# PCB-BI8-2x5C3.net
KiCad netlist of a schematic drawn in EAGLE
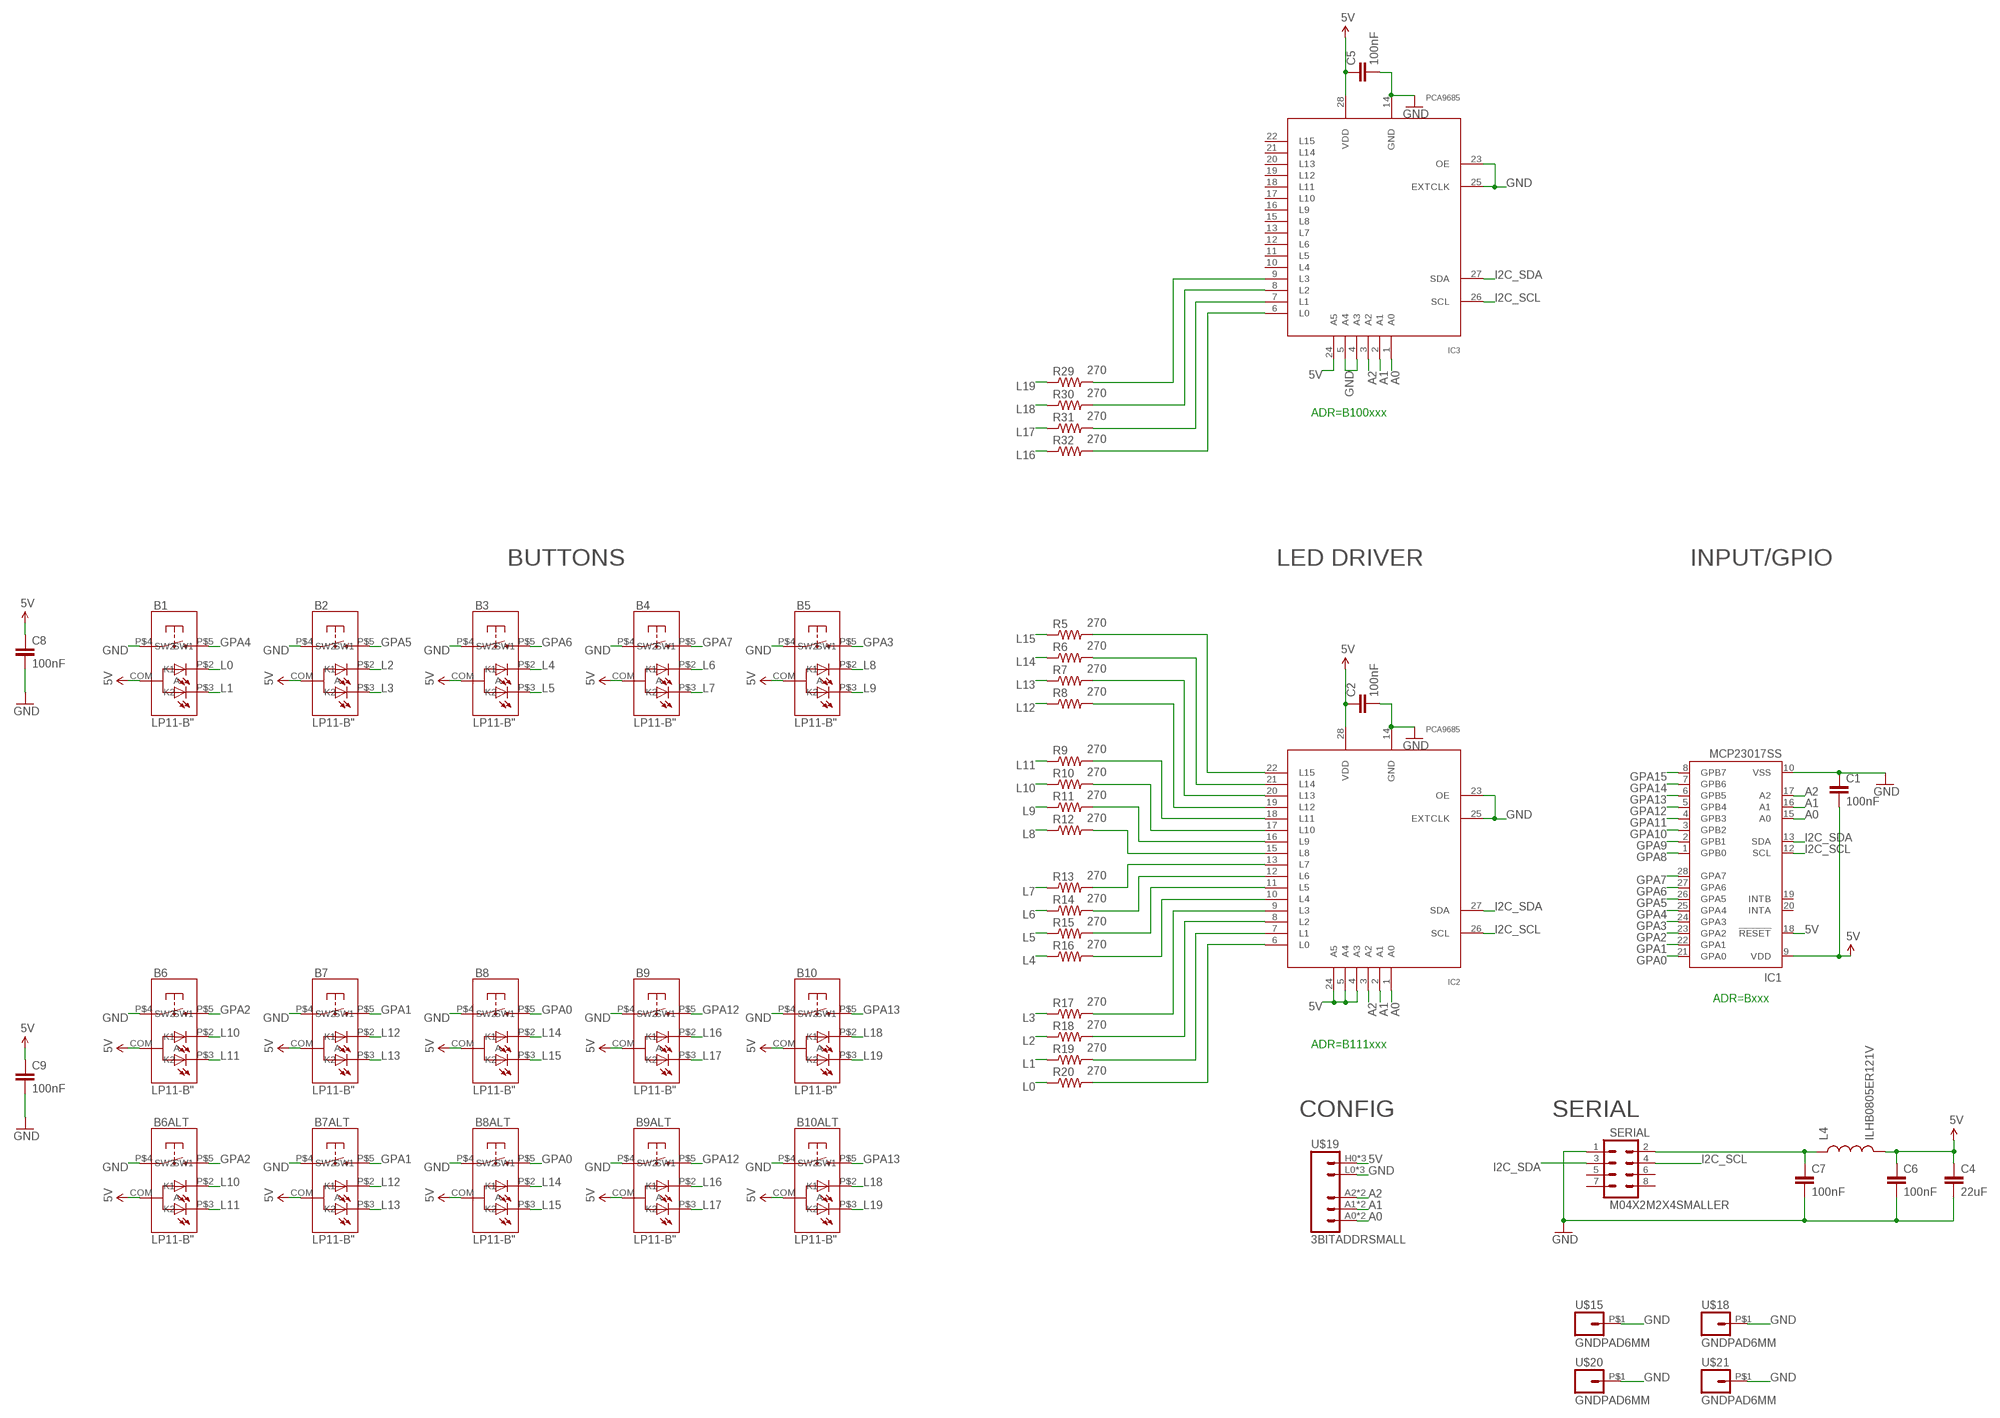
[diagram p0: schematic, sheet 1]

(export (version "E")
  (design (tool "Eeschema 10.0.6"))
  (components
    (comp (ref "B1")
      (value "LP11-B\"")
      (footprint "eagle-import:LP11")
      (libsource (lib "eagle-import") (part "LP11-B{dblquote}"))
    )
    (comp (ref "B2")
      (value "LP11-B\"")
      (footprint "eagle-import:LP11")
      (libsource (lib "eagle-import") (part "LP11-B{dblquote}"))
    )
    (comp (ref "B3")
      (value "LP11-B\"")
      (footprint "eagle-import:LP11")
      (libsource (lib "eagle-import") (part "LP11-B{dblquote}"))
    )
    (comp (ref "B4")
      (value "LP11-B\"")
      (footprint "eagle-import:LP11")
      (libsource (lib "eagle-import") (part "LP11-B{dblquote}"))
    )
    (comp (ref "B5")
      (value "LP11-B\"")
      (footprint "eagle-import:LP11")
      (libsource (lib "eagle-import") (part "LP11-B{dblquote}"))
    )
    (comp (ref "B6")
      (value "LP11-B\"")
      (footprint "eagle-import:LP11")
      (libsource (lib "eagle-import") (part "LP11-B{dblquote}"))
    )
    (comp (ref "B6ALT")
      (value "LP11-B\"")
      (footprint "eagle-import:LP11")
      (libsource (lib "eagle-import") (part "LP11-B{dblquote}"))
    )
    (comp (ref "B7")
      (value "LP11-B\"")
      (footprint "eagle-import:LP11")
      (libsource (lib "eagle-import") (part "LP11-B{dblquote}"))
    )
    (comp (ref "B7ALT")
      (value "LP11-B\"")
      (footprint "eagle-import:LP11")
      (libsource (lib "eagle-import") (part "LP11-B{dblquote}"))
    )
    (comp (ref "B8")
      (value "LP11-B\"")
      (footprint "eagle-import:LP11")
      (libsource (lib "eagle-import") (part "LP11-B{dblquote}"))
    )
    (comp (ref "B8ALT")
      (value "LP11-B\"")
      (footprint "eagle-import:LP11")
      (libsource (lib "eagle-import") (part "LP11-B{dblquote}"))
    )
    (comp (ref "B9")
      (value "LP11-B\"")
      (footprint "eagle-import:LP11")
      (libsource (lib "eagle-import") (part "LP11-B{dblquote}"))
    )
    (comp (ref "B9ALT")
      (value "LP11-B\"")
      (footprint "eagle-import:LP11")
      (libsource (lib "eagle-import") (part "LP11-B{dblquote}"))
    )
    (comp (ref "B10")
      (value "LP11-B\"")
      (footprint "eagle-import:LP11")
      (libsource (lib "eagle-import") (part "LP11-B{dblquote}"))
    )
    (comp (ref "B10ALT")
      (value "LP11-B\"")
      (footprint "eagle-import:LP11")
      (libsource (lib "eagle-import") (part "LP11-B{dblquote}"))
    )
    (comp (ref "C1")
      (value "100nF")
      (footprint "eagle-import:0603-CAP")
      (libsource (lib "eagle-import") (part "CAP0603-CAP"))
    )
    (comp (ref "C2")
      (value "100nF")
      (footprint "eagle-import:0603-CAP")
      (libsource (lib "eagle-import") (part "CAP0603-CAP"))
    )
    (comp (ref "C4")
      (value "22uF")
      (footprint "eagle-import:0805")
      (libsource (lib "eagle-import") (part "CAP0805"))
    )
    (comp (ref "C5")
      (value "100nF")
      (footprint "eagle-import:0603-CAP")
      (libsource (lib "eagle-import") (part "CAP0603-CAP"))
    )
    (comp (ref "C6")
      (value "100nF")
      (footprint "eagle-import:0603-CAP")
      (libsource (lib "eagle-import") (part "CAP0603-CAP"))
    )
    (comp (ref "C7")
      (value "100nF")
      (footprint "eagle-import:0603-CAP")
      (libsource (lib "eagle-import") (part "CAP0603-CAP"))
    )
    (comp (ref "C8")
      (value "100nF")
      (footprint "eagle-import:0603-CAP")
      (libsource (lib "eagle-import") (part "CAP0603-CAP"))
    )
    (comp (ref "C9")
      (value "100nF")
      (footprint "eagle-import:0603-CAP")
      (libsource (lib "eagle-import") (part "CAP0603-CAP"))
    )
    (comp (ref "IC1")
      (value "MCP23017SS")
      (footprint "eagle-import:SSOP28")
      (fields
        (field (name "MF") "MICROCHIP")
        (field (name "MPN") "MCP23017-E/SS")
        (field (name "MPN_1") "MCP23017-E/SS")
        (field (name "OC_FARNELL") "1467674")
        (field (name "OC_NEWARK") "31K2960")
      )
      (libsource (lib "eagle-import") (part "MCP23017SS"))
    )
    (comp (ref "IC2")
      (value "PCA9685")
      (footprint "eagle-import:TSSOP28")
      (libsource (lib "eagle-import") (part "PCA9685"))
    )
    (comp (ref "IC3")
      (value "PCA9685")
      (footprint "eagle-import:TSSOP28")
      (libsource (lib "eagle-import") (part "PCA9685"))
    )
    (comp (ref "L4")
      (value "ILHB0805ER121V")
      (footprint "eagle-import:0805")
      (libsource (lib "eagle-import") (part "INDUCTOR0805"))
    )
    (comp (ref "R5")
      (value "270")
      (footprint "eagle-import:0603-RES")
      (libsource (lib "eagle-import") (part "RESISTOR0603-RES"))
    )
    (comp (ref "R6")
      (value "270")
      (footprint "eagle-import:0603-RES")
      (libsource (lib "eagle-import") (part "RESISTOR0603-RES"))
    )
    (comp (ref "R7")
      (value "270")
      (footprint "eagle-import:0603-RES")
      (libsource (lib "eagle-import") (part "RESISTOR0603-RES"))
    )
    (comp (ref "R8")
      (value "270")
      (footprint "eagle-import:0603-RES")
      (libsource (lib "eagle-import") (part "RESISTOR0603-RES"))
    )
    (comp (ref "R9")
      (value "270")
      (footprint "eagle-import:0603-RES")
      (libsource (lib "eagle-import") (part "RESISTOR0603-RES"))
    )
    (comp (ref "R10")
      (value "270")
      (footprint "eagle-import:0603-RES")
      (libsource (lib "eagle-import") (part "RESISTOR0603-RES"))
    )
    (comp (ref "R11")
      (value "270")
      (footprint "eagle-import:0603-RES")
      (libsource (lib "eagle-import") (part "RESISTOR0603-RES"))
    )
    (comp (ref "R12")
      (value "270")
      (footprint "eagle-import:0603-RES")
      (libsource (lib "eagle-import") (part "RESISTOR0603-RES"))
    )
    (comp (ref "R13")
      (value "270")
      (footprint "eagle-import:0603-RES")
      (libsource (lib "eagle-import") (part "RESISTOR0603-RES"))
    )
    (comp (ref "R14")
      (value "270")
      (footprint "eagle-import:0603-RES")
      (libsource (lib "eagle-import") (part "RESISTOR0603-RES"))
    )
    (comp (ref "R15")
      (value "270")
      (footprint "eagle-import:0603-RES")
      (libsource (lib "eagle-import") (part "RESISTOR0603-RES"))
    )
    (comp (ref "R16")
      (value "270")
      (footprint "eagle-import:0603-RES")
      (libsource (lib "eagle-import") (part "RESISTOR0603-RES"))
    )
    (comp (ref "R17")
      (value "270")
      (footprint "eagle-import:0603-RES")
      (libsource (lib "eagle-import") (part "RESISTOR0603-RES"))
    )
    (comp (ref "R18")
      (value "270")
      (footprint "eagle-import:0603-RES")
      (libsource (lib "eagle-import") (part "RESISTOR0603-RES"))
    )
    (comp (ref "R19")
      (value "270")
      (footprint "eagle-import:0603-RES")
      (libsource (lib "eagle-import") (part "RESISTOR0603-RES"))
    )
    (comp (ref "R20")
      (value "270")
      (footprint "eagle-import:0603-RES")
      (libsource (lib "eagle-import") (part "RESISTOR0603-RES"))
    )
    (comp (ref "R29")
      (value "270")
      (footprint "eagle-import:0603-RES")
      (libsource (lib "eagle-import") (part "RESISTOR0603-RES"))
    )
    (comp (ref "R30")
      (value "270")
      (footprint "eagle-import:0603-RES")
      (libsource (lib "eagle-import") (part "RESISTOR0603-RES"))
    )
    (comp (ref "R31")
      (value "270")
      (footprint "eagle-import:0603-RES")
      (libsource (lib "eagle-import") (part "RESISTOR0603-RES"))
    )
    (comp (ref "R32")
      (value "270")
      (footprint "eagle-import:0603-RES")
      (libsource (lib "eagle-import") (part "RESISTOR0603-RES"))
    )
    (comp (ref "SERIAL")
      (value "M04X2M2X4SMALLER")
      (footprint "eagle-import:M2X4SMALLER")
      (libsource (lib "eagle-import") (part "M04X2M2X4SMALLER"))
    )
    (comp (ref "U$15")
      (value "GNDPAD6MM")
      (footprint "eagle-import:3.2MMPAD6MM")
      (libsource (lib "eagle-import") (part "GNDPAD6MM"))
    )
    (comp (ref "U$18")
      (value "GNDPAD6MM")
      (footprint "eagle-import:3.2MMPAD6MM")
      (libsource (lib "eagle-import") (part "GNDPAD6MM"))
    )
    (comp (ref "U$19")
      (value "3BITADDRSMALL")
      (footprint "eagle-import:3BITADDR_SMALL")
      (libsource (lib "eagle-import") (part "3BITADDRSMALL"))
    )
    (comp (ref "U$20")
      (value "GNDPAD6MM")
      (footprint "eagle-import:3.2MMPAD6MM")
      (libsource (lib "eagle-import") (part "GNDPAD6MM"))
    )
    (comp (ref "U$21")
      (value "GNDPAD6MM")
      (footprint "eagle-import:3.2MMPAD6MM")
      (libsource (lib "eagle-import") (part "GNDPAD6MM"))
    )
  )
  (nets
    (net (code "1") (name "5V") (class "Default")
      (node (ref "B1") (pin "COM") (pinfunction "A_COM") (pintype "bidirectional"))
      (node (ref "B10") (pin "COM") (pinfunction "A_COM") (pintype "bidirectional"))
      (node (ref "B10ALT") (pin "COM") (pinfunction "A_COM") (pintype "bidirectional"))
      (node (ref "B2") (pin "COM") (pinfunction "A_COM") (pintype "bidirectional"))
      (node (ref "B3") (pin "COM") (pinfunction "A_COM") (pintype "bidirectional"))
      (node (ref "B4") (pin "COM") (pinfunction "A_COM") (pintype "bidirectional"))
      (node (ref "B5") (pin "COM") (pinfunction "A_COM") (pintype "bidirectional"))
      (node (ref "B6") (pin "COM") (pinfunction "A_COM") (pintype "bidirectional"))
      (node (ref "B6ALT") (pin "COM") (pinfunction "A_COM") (pintype "bidirectional"))
      (node (ref "B7") (pin "COM") (pinfunction "A_COM") (pintype "bidirectional"))
      (node (ref "B7ALT") (pin "COM") (pinfunction "A_COM") (pintype "bidirectional"))
      (node (ref "B8") (pin "COM") (pinfunction "A_COM") (pintype "bidirectional"))
      (node (ref "B8ALT") (pin "COM") (pinfunction "A_COM") (pintype "bidirectional"))
      (node (ref "B9") (pin "COM") (pinfunction "A_COM") (pintype "bidirectional"))
      (node (ref "B9ALT") (pin "COM") (pinfunction "A_COM") (pintype "bidirectional"))
      (node (ref "C1") (pin "2") (pinfunction "2_2") (pintype "passive"))
      (node (ref "C2") (pin "1") (pinfunction "1_1") (pintype "passive"))
      (node (ref "C4") (pin "1") (pinfunction "1_1") (pintype "passive"))
      (node (ref "C5") (pin "1") (pinfunction "1_1") (pintype "passive"))
      (node (ref "C6") (pin "1") (pinfunction "1_1") (pintype "passive"))
      (node (ref "C8") (pin "1") (pinfunction "1_1") (pintype "passive"))
      (node (ref "C9") (pin "1") (pinfunction "1_1") (pintype "passive"))
      (node (ref "IC1") (pin "18") (pinfunction "~{RESET}_18") (pintype "input"))
      (node (ref "IC1") (pin "9") (pinfunction "VDD_9") (pintype "power_in"))
      (node (ref "IC2") (pin "24") (pinfunction "A5_24") (pintype "input"))
      (node (ref "IC2") (pin "28") (pinfunction "VDD_28") (pintype "power_in"))
      (node (ref "IC2") (pin "4") (pinfunction "A3_4") (pintype "input"))
      (node (ref "IC2") (pin "5") (pinfunction "A4_5") (pintype "input"))
      (node (ref "IC3") (pin "24") (pinfunction "A5_24") (pintype "input"))
      (node (ref "IC3") (pin "28") (pinfunction "VDD_28") (pintype "power_in"))
      (node (ref "L4") (pin "2") (pinfunction "2_2") (pintype "passive"))
      (node (ref "U$19") (pin "H0") (pinfunction "VCC_H0") (pintype "passive"))
      (node (ref "U$19") (pin "H1") (pinfunction "VCC_H1") (pintype "passive"))
      (node (ref "U$19") (pin "H2") (pinfunction "VCC_H2") (pintype "passive"))
    )
    (net (code "2") (name "A0") (class "Default")
      (node (ref "IC1") (pin "15") (pinfunction "A0_15") (pintype "input"))
      (node (ref "IC2") (pin "1") (pinfunction "A0_1") (pintype "input"))
      (node (ref "IC3") (pin "1") (pinfunction "A0_1") (pintype "input"))
      (node (ref "U$19") (pin "A0") (pinfunction "A0_A0") (pintype "passive"))
      (node (ref "U$19") (pin "AS0") (pinfunction "A0_AS0") (pintype "passive"))
    )
    (net (code "3") (name "A1") (class "Default")
      (node (ref "IC1") (pin "16") (pinfunction "A1_16") (pintype "input"))
      (node (ref "IC2") (pin "2") (pinfunction "A1_2") (pintype "input"))
      (node (ref "IC3") (pin "2") (pinfunction "A1_2") (pintype "input"))
      (node (ref "U$19") (pin "A1") (pinfunction "A1_A1") (pintype "passive"))
      (node (ref "U$19") (pin "AS1") (pinfunction "A1_AS1") (pintype "passive"))
    )
    (net (code "4") (name "A2") (class "Default")
      (node (ref "IC1") (pin "17") (pinfunction "A2_17") (pintype "input"))
      (node (ref "IC2") (pin "3") (pinfunction "A2_3") (pintype "input"))
      (node (ref "IC3") (pin "3") (pinfunction "A2_3") (pintype "input"))
      (node (ref "U$19") (pin "A2") (pinfunction "A2_A2") (pintype "passive"))
      (node (ref "U$19") (pin "AS2") (pinfunction "A2_AS2") (pintype "passive"))
    )
    (net (code "5") (name "GND") (class "Default")
      (node (ref "B1") (pin "P$4") (pinfunction "SW1_P$4") (pintype "bidirectional"))
      (node (ref "B10") (pin "P$4") (pinfunction "SW1_P$4") (pintype "bidirectional"))
      (node (ref "B10ALT") (pin "P$4") (pinfunction "SW1_P$4") (pintype "bidirectional"))
      (node (ref "B2") (pin "P$4") (pinfunction "SW1_P$4") (pintype "bidirectional"))
      (node (ref "B3") (pin "P$4") (pinfunction "SW1_P$4") (pintype "bidirectional"))
      (node (ref "B4") (pin "P$4") (pinfunction "SW1_P$4") (pintype "bidirectional"))
      (node (ref "B5") (pin "P$4") (pinfunction "SW1_P$4") (pintype "bidirectional"))
      (node (ref "B6") (pin "P$4") (pinfunction "SW1_P$4") (pintype "bidirectional"))
      (node (ref "B6ALT") (pin "P$4") (pinfunction "SW1_P$4") (pintype "bidirectional"))
      (node (ref "B7") (pin "P$4") (pinfunction "SW1_P$4") (pintype "bidirectional"))
      (node (ref "B7ALT") (pin "P$4") (pinfunction "SW1_P$4") (pintype "bidirectional"))
      (node (ref "B8") (pin "P$4") (pinfunction "SW1_P$4") (pintype "bidirectional"))
      (node (ref "B8ALT") (pin "P$4") (pinfunction "SW1_P$4") (pintype "bidirectional"))
      (node (ref "B9") (pin "P$4") (pinfunction "SW1_P$4") (pintype "bidirectional"))
      (node (ref "B9ALT") (pin "P$4") (pinfunction "SW1_P$4") (pintype "bidirectional"))
      (node (ref "C1") (pin "1") (pinfunction "1_1") (pintype "passive"))
      (node (ref "C2") (pin "2") (pinfunction "2_2") (pintype "passive"))
      (node (ref "C4") (pin "2") (pinfunction "2_2") (pintype "passive"))
      (node (ref "C5") (pin "2") (pinfunction "2_2") (pintype "passive"))
      (node (ref "C6") (pin "2") (pinfunction "2_2") (pintype "passive"))
      (node (ref "C7") (pin "2") (pinfunction "2_2") (pintype "passive"))
      (node (ref "C8") (pin "2") (pinfunction "2_2") (pintype "passive"))
      (node (ref "C9") (pin "2") (pinfunction "2_2") (pintype "passive"))
      (node (ref "IC1") (pin "10") (pinfunction "VSS_10") (pintype "power_in"))
      (node (ref "IC2") (pin "14") (pinfunction "GND_14") (pintype "power_in"))
      (node (ref "IC2") (pin "23") (pinfunction "OE_23") (pintype "input"))
      (node (ref "IC2") (pin "25") (pinfunction "EXTCLK_25") (pintype "input"))
      (node (ref "IC3") (pin "14") (pinfunction "GND_14") (pintype "power_in"))
      (node (ref "IC3") (pin "23") (pinfunction "OE_23") (pintype "input"))
      (node (ref "IC3") (pin "25") (pinfunction "EXTCLK_25") (pintype "input"))
      (node (ref "IC3") (pin "4") (pinfunction "A3_4") (pintype "input"))
      (node (ref "IC3") (pin "5") (pinfunction "A4_5") (pintype "input"))
      (node (ref "SERIAL") (pin "1") (pinfunction "1_1") (pintype "passive"))
      (node (ref "U$15") (pin "P$1") (pinfunction "1_P$1") (pintype "passive"))
      (node (ref "U$18") (pin "P$1") (pinfunction "1_P$1") (pintype "passive"))
      (node (ref "U$19") (pin "L0") (pinfunction "GND_L0") (pintype "passive"))
      (node (ref "U$19") (pin "L1") (pinfunction "GND_L1") (pintype "passive"))
      (node (ref "U$19") (pin "L2") (pinfunction "GND_L2") (pintype "passive"))
      (node (ref "U$20") (pin "P$1") (pinfunction "1_P$1") (pintype "passive"))
      (node (ref "U$21") (pin "P$1") (pinfunction "1_P$1") (pintype "passive"))
    )
    (net (code "6") (name "GPA0") (class "Default")
      (node (ref "B8") (pin "P$5") (pinfunction "SW2_P$5") (pintype "bidirectional"))
      (node (ref "B8ALT") (pin "P$5") (pinfunction "SW2_P$5") (pintype "bidirectional"))
      (node (ref "IC1") (pin "21") (pinfunction "GPA0_21") (pintype "bidirectional"))
    )
    (net (code "7") (name "GPA1") (class "Default")
      (node (ref "B7") (pin "P$5") (pinfunction "SW2_P$5") (pintype "bidirectional"))
      (node (ref "B7ALT") (pin "P$5") (pinfunction "SW2_P$5") (pintype "bidirectional"))
      (node (ref "IC1") (pin "22") (pinfunction "GPA1_22") (pintype "bidirectional"))
    )
    (net (code "8") (name "GPA2") (class "Default")
      (node (ref "B6") (pin "P$5") (pinfunction "SW2_P$5") (pintype "bidirectional"))
      (node (ref "B6ALT") (pin "P$5") (pinfunction "SW2_P$5") (pintype "bidirectional"))
      (node (ref "IC1") (pin "23") (pinfunction "GPA2_23") (pintype "bidirectional"))
    )
    (net (code "9") (name "GPA3") (class "Default")
      (node (ref "B5") (pin "P$5") (pinfunction "SW2_P$5") (pintype "bidirectional"))
      (node (ref "IC1") (pin "24") (pinfunction "GPA3_24") (pintype "bidirectional"))
    )
    (net (code "10") (name "GPA4") (class "Default")
      (node (ref "B1") (pin "P$5") (pinfunction "SW2_P$5") (pintype "bidirectional"))
      (node (ref "IC1") (pin "25") (pinfunction "GPA4_25") (pintype "bidirectional"))
    )
    (net (code "11") (name "GPA5") (class "Default")
      (node (ref "B2") (pin "P$5") (pinfunction "SW2_P$5") (pintype "bidirectional"))
      (node (ref "IC1") (pin "26") (pinfunction "GPA5_26") (pintype "bidirectional"))
    )
    (net (code "12") (name "GPA6") (class "Default")
      (node (ref "B3") (pin "P$5") (pinfunction "SW2_P$5") (pintype "bidirectional"))
      (node (ref "IC1") (pin "27") (pinfunction "GPA6_27") (pintype "bidirectional"))
    )
    (net (code "13") (name "GPA7") (class "Default")
      (node (ref "B4") (pin "P$5") (pinfunction "SW2_P$5") (pintype "bidirectional"))
      (node (ref "IC1") (pin "28") (pinfunction "GPA7_28") (pintype "bidirectional"))
    )
    (net (code "14") (name "GPA8") (class "Default")
      (node (ref "IC1") (pin "1") (pinfunction "GPB0_1") (pintype "bidirectional"))
    )
    (net (code "15") (name "GPA9") (class "Default")
      (node (ref "IC1") (pin "2") (pinfunction "GPB1_2") (pintype "bidirectional"))
    )
    (net (code "16") (name "GPA10") (class "Default")
      (node (ref "IC1") (pin "3") (pinfunction "GPB2_3") (pintype "bidirectional"))
    )
    (net (code "17") (name "GPA11") (class "Default")
      (node (ref "IC1") (pin "4") (pinfunction "GPB3_4") (pintype "bidirectional"))
    )
    (net (code "18") (name "GPA12") (class "Default")
      (node (ref "B9") (pin "P$5") (pinfunction "SW2_P$5") (pintype "bidirectional"))
      (node (ref "B9ALT") (pin "P$5") (pinfunction "SW2_P$5") (pintype "bidirectional"))
      (node (ref "IC1") (pin "5") (pinfunction "GPB4_5") (pintype "bidirectional"))
    )
    (net (code "19") (name "GPA13") (class "Default")
      (node (ref "B10") (pin "P$5") (pinfunction "SW2_P$5") (pintype "bidirectional"))
      (node (ref "B10ALT") (pin "P$5") (pinfunction "SW2_P$5") (pintype "bidirectional"))
      (node (ref "IC1") (pin "6") (pinfunction "GPB5_6") (pintype "bidirectional"))
    )
    (net (code "20") (name "GPA14") (class "Default")
      (node (ref "IC1") (pin "7") (pinfunction "GPB6_7") (pintype "bidirectional"))
    )
    (net (code "21") (name "GPA15") (class "Default")
      (node (ref "IC1") (pin "8") (pinfunction "GPB7_8") (pintype "bidirectional"))
    )
    (net (code "22") (name "I2C_SCL") (class "Default")
      (node (ref "IC1") (pin "12") (pinfunction "SCL_12") (pintype "input"))
      (node (ref "IC2") (pin "26") (pinfunction "SCL_26") (pintype "input"))
      (node (ref "IC3") (pin "26") (pinfunction "SCL_26") (pintype "input"))
      (node (ref "SERIAL") (pin "4") (pinfunction "4_4") (pintype "passive"))
    )
    (net (code "23") (name "I2C_SDA") (class "Default")
      (node (ref "IC1") (pin "13") (pinfunction "SDA_13") (pintype "bidirectional"))
      (node (ref "IC2") (pin "27") (pinfunction "SDA_27") (pintype "input"))
      (node (ref "IC3") (pin "27") (pinfunction "SDA_27") (pintype "input"))
      (node (ref "SERIAL") (pin "3") (pinfunction "3_3") (pintype "passive"))
    )
    (net (code "24") (name "L0") (class "Default")
      (node (ref "B1") (pin "P$2") (pinfunction "K1_P$2") (pintype "bidirectional"))
      (node (ref "R20") (pin "1") (pinfunction "1_1") (pintype "passive"))
    )
    (net (code "25") (name "L1") (class "Default")
      (node (ref "B1") (pin "P$3") (pinfunction "K2_P$3") (pintype "bidirectional"))
      (node (ref "R19") (pin "1") (pinfunction "1_1") (pintype "passive"))
    )
    (net (code "26") (name "L2") (class "Default")
      (node (ref "B2") (pin "P$2") (pinfunction "K1_P$2") (pintype "bidirectional"))
      (node (ref "R18") (pin "1") (pinfunction "1_1") (pintype "passive"))
    )
    (net (code "27") (name "L3") (class "Default")
      (node (ref "B2") (pin "P$3") (pinfunction "K2_P$3") (pintype "bidirectional"))
      (node (ref "R17") (pin "1") (pinfunction "1_1") (pintype "passive"))
    )
    (net (code "28") (name "L4") (class "Default")
      (node (ref "B3") (pin "P$2") (pinfunction "K1_P$2") (pintype "bidirectional"))
      (node (ref "R16") (pin "1") (pinfunction "1_1") (pintype "passive"))
    )
    (net (code "29") (name "L5") (class "Default")
      (node (ref "B3") (pin "P$3") (pinfunction "K2_P$3") (pintype "bidirectional"))
      (node (ref "R15") (pin "1") (pinfunction "1_1") (pintype "passive"))
    )
    (net (code "30") (name "L6") (class "Default")
      (node (ref "B4") (pin "P$2") (pinfunction "K1_P$2") (pintype "bidirectional"))
      (node (ref "R14") (pin "1") (pinfunction "1_1") (pintype "passive"))
    )
    (net (code "31") (name "L7") (class "Default")
      (node (ref "B4") (pin "P$3") (pinfunction "K2_P$3") (pintype "bidirectional"))
      (node (ref "R13") (pin "1") (pinfunction "1_1") (pintype "passive"))
    )
    (net (code "32") (name "L8") (class "Default")
      (node (ref "B5") (pin "P$2") (pinfunction "K1_P$2") (pintype "bidirectional"))
      (node (ref "R12") (pin "1") (pinfunction "1_1") (pintype "passive"))
    )
    (net (code "33") (name "L9") (class "Default")
      (node (ref "B5") (pin "P$3") (pinfunction "K2_P$3") (pintype "bidirectional"))
      (node (ref "R11") (pin "1") (pinfunction "1_1") (pintype "passive"))
    )
    (net (code "34") (name "L10") (class "Default")
      (node (ref "B6") (pin "P$2") (pinfunction "K1_P$2") (pintype "bidirectional"))
      (node (ref "B6ALT") (pin "P$2") (pinfunction "K1_P$2") (pintype "bidirectional"))
      (node (ref "R10") (pin "1") (pinfunction "1_1") (pintype "passive"))
    )
    (net (code "35") (name "L11") (class "Default")
      (node (ref "B6") (pin "P$3") (pinfunction "K2_P$3") (pintype "bidirectional"))
      (node (ref "B6ALT") (pin "P$3") (pinfunction "K2_P$3") (pintype "bidirectional"))
      (node (ref "R9") (pin "1") (pinfunction "1_1") (pintype "passive"))
    )
    (net (code "36") (name "L12") (class "Default")
      (node (ref "B7") (pin "P$2") (pinfunction "K1_P$2") (pintype "bidirectional"))
      (node (ref "B7ALT") (pin "P$2") (pinfunction "K1_P$2") (pintype "bidirectional"))
      (node (ref "R8") (pin "1") (pinfunction "1_1") (pintype "passive"))
    )
    (net (code "37") (name "L13") (class "Default")
      (node (ref "B7") (pin "P$3") (pinfunction "K2_P$3") (pintype "bidirectional"))
      (node (ref "B7ALT") (pin "P$3") (pinfunction "K2_P$3") (pintype "bidirectional"))
      (node (ref "R7") (pin "1") (pinfunction "1_1") (pintype "passive"))
    )
    (net (code "38") (name "L14") (class "Default")
      (node (ref "B8") (pin "P$2") (pinfunction "K1_P$2") (pintype "bidirectional"))
      (node (ref "B8ALT") (pin "P$2") (pinfunction "K1_P$2") (pintype "bidirectional"))
      (node (ref "R6") (pin "1") (pinfunction "1_1") (pintype "passive"))
    )
    (net (code "39") (name "L15") (class "Default")
      (node (ref "B8") (pin "P$3") (pinfunction "K2_P$3") (pintype "bidirectional"))
      (node (ref "B8ALT") (pin "P$3") (pinfunction "K2_P$3") (pintype "bidirectional"))
      (node (ref "R5") (pin "1") (pinfunction "1_1") (pintype "passive"))
    )
    (net (code "40") (name "L16") (class "Default")
      (node (ref "B9") (pin "P$2") (pinfunction "K1_P$2") (pintype "bidirectional"))
      (node (ref "B9ALT") (pin "P$2") (pinfunction "K1_P$2") (pintype "bidirectional"))
      (node (ref "R32") (pin "1") (pinfunction "1_1") (pintype "passive"))
    )
    (net (code "41") (name "L17") (class "Default")
      (node (ref "B9") (pin "P$3") (pinfunction "K2_P$3") (pintype "bidirectional"))
      (node (ref "B9ALT") (pin "P$3") (pinfunction "K2_P$3") (pintype "bidirectional"))
      (node (ref "R31") (pin "1") (pinfunction "1_1") (pintype "passive"))
    )
    (net (code "42") (name "L18") (class "Default")
      (node (ref "B10") (pin "P$2") (pinfunction "K1_P$2") (pintype "bidirectional"))
      (node (ref "B10ALT") (pin "P$2") (pinfunction "K1_P$2") (pintype "bidirectional"))
      (node (ref "R30") (pin "1") (pinfunction "1_1") (pintype "passive"))
    )
    (net (code "43") (name "L19") (class "Default")
      (node (ref "B10") (pin "P$3") (pinfunction "K2_P$3") (pintype "bidirectional"))
      (node (ref "B10ALT") (pin "P$3") (pinfunction "K2_P$3") (pintype "bidirectional"))
      (node (ref "R29") (pin "1") (pinfunction "1_1") (pintype "passive"))
    )
    (net (code "44") (name "Net-(C7-Pad1)") (class "Default")
      (node (ref "C7") (pin "1") (pinfunction "1_1") (pintype "passive"))
      (node (ref "L4") (pin "1") (pinfunction "1_1") (pintype "passive"))
      (node (ref "SERIAL") (pin "2") (pinfunction "2_2") (pintype "passive"))
    )
    (net (code "45") (name "Net-(IC2-L0)") (class "Default")
      (node (ref "IC2") (pin "6") (pinfunction "L0_6") (pintype "output"))
      (node (ref "R20") (pin "2") (pinfunction "2_2") (pintype "passive"))
    )
    (net (code "46") (name "Net-(IC2-L1)") (class "Default")
      (node (ref "IC2") (pin "7") (pinfunction "L1_7") (pintype "output"))
      (node (ref "R19") (pin "2") (pinfunction "2_2") (pintype "passive"))
    )
    (net (code "47") (name "Net-(IC2-L2)") (class "Default")
      (node (ref "IC2") (pin "8") (pinfunction "L2_8") (pintype "output"))
      (node (ref "R18") (pin "2") (pinfunction "2_2") (pintype "passive"))
    )
    (net (code "48") (name "Net-(IC2-L3)") (class "Default")
      (node (ref "IC2") (pin "9") (pinfunction "L3_9") (pintype "output"))
      (node (ref "R17") (pin "2") (pinfunction "2_2") (pintype "passive"))
    )
    (net (code "49") (name "Net-(IC2-L4)") (class "Default")
      (node (ref "IC2") (pin "10") (pinfunction "L4_10") (pintype "output"))
      (node (ref "R16") (pin "2") (pinfunction "2_2") (pintype "passive"))
    )
    (net (code "50") (name "Net-(IC2-L5)") (class "Default")
      (node (ref "IC2") (pin "11") (pinfunction "L5_11") (pintype "output"))
      (node (ref "R15") (pin "2") (pinfunction "2_2") (pintype "passive"))
    )
    (net (code "51") (name "Net-(IC2-L6)") (class "Default")
      (node (ref "IC2") (pin "12") (pinfunction "L6_12") (pintype "output"))
      (node (ref "R14") (pin "2") (pinfunction "2_2") (pintype "passive"))
    )
    (net (code "52") (name "Net-(IC2-L7)") (class "Default")
      (node (ref "IC2") (pin "13") (pinfunction "L7_13") (pintype "output"))
      (node (ref "R13") (pin "2") (pinfunction "2_2") (pintype "passive"))
    )
    (net (code "53") (name "Net-(IC2-L8)") (class "Default")
      (node (ref "IC2") (pin "15") (pinfunction "L8_15") (pintype "output"))
      (node (ref "R12") (pin "2") (pinfunction "2_2") (pintype "passive"))
    )
    (net (code "54") (name "Net-(IC2-L9)") (class "Default")
      (node (ref "IC2") (pin "16") (pinfunction "L9_16") (pintype "output"))
      (node (ref "R11") (pin "2") (pinfunction "2_2") (pintype "passive"))
    )
    (net (code "55") (name "Net-(IC2-L10)") (class "Default")
      (node (ref "IC2") (pin "17") (pinfunction "L10_17") (pintype "output"))
      (node (ref "R10") (pin "2") (pinfunction "2_2") (pintype "passive"))
    )
    (net (code "56") (name "Net-(IC2-L11)") (class "Default")
      (node (ref "IC2") (pin "18") (pinfunction "L11_18") (pintype "output"))
      (node (ref "R9") (pin "2") (pinfunction "2_2") (pintype "passive"))
    )
    (net (code "57") (name "Net-(IC2-L12)") (class "Default")
      (node (ref "IC2") (pin "19") (pinfunction "L12_19") (pintype "output"))
      (node (ref "R8") (pin "2") (pinfunction "2_2") (pintype "passive"))
    )
    (net (code "58") (name "Net-(IC2-L13)") (class "Default")
      (node (ref "IC2") (pin "20") (pinfunction "L13_20") (pintype "output"))
      (node (ref "R7") (pin "2") (pinfunction "2_2") (pintype "passive"))
    )
    (net (code "59") (name "Net-(IC2-L14)") (class "Default")
      (node (ref "IC2") (pin "21") (pinfunction "L14_21") (pintype "output"))
      (node (ref "R6") (pin "2") (pinfunction "2_2") (pintype "passive"))
    )
    (net (code "60") (name "Net-(IC2-L15)") (class "Default")
      (node (ref "IC2") (pin "22") (pinfunction "L15_22") (pintype "output"))
      (node (ref "R5") (pin "2") (pinfunction "2_2") (pintype "passive"))
    )
    (net (code "61") (name "Net-(IC3-L0)") (class "Default")
      (node (ref "IC3") (pin "6") (pinfunction "L0_6") (pintype "output"))
      (node (ref "R32") (pin "2") (pinfunction "2_2") (pintype "passive"))
    )
    (net (code "62") (name "Net-(IC3-L1)") (class "Default")
      (node (ref "IC3") (pin "7") (pinfunction "L1_7") (pintype "output"))
      (node (ref "R31") (pin "2") (pinfunction "2_2") (pintype "passive"))
    )
    (net (code "63") (name "Net-(IC3-L2)") (class "Default")
      (node (ref "IC3") (pin "8") (pinfunction "L2_8") (pintype "output"))
      (node (ref "R30") (pin "2") (pinfunction "2_2") (pintype "passive"))
    )
    (net (code "64") (name "Net-(IC3-L3)") (class "Default")
      (node (ref "IC3") (pin "9") (pinfunction "L3_9") (pintype "output"))
      (node (ref "R29") (pin "2") (pinfunction "2_2") (pintype "passive"))
    )
    (net (code "65") (name "unconnected-(IC1-INTA-Pad20)") (class "Default")
      (node (ref "IC1") (pin "20") (pinfunction "INTA_20") (pintype "output"))
    )
    (net (code "66") (name "unconnected-(IC1-INTB-Pad19)") (class "Default")
      (node (ref "IC1") (pin "19") (pinfunction "INTB_19") (pintype "output"))
    )
    (net (code "67") (name "unconnected-(IC3-L4-Pad10)") (class "Default")
      (node (ref "IC3") (pin "10") (pinfunction "L4_10") (pintype "output"))
    )
    (net (code "68") (name "unconnected-(IC3-L5-Pad11)") (class "Default")
      (node (ref "IC3") (pin "11") (pinfunction "L5_11") (pintype "output"))
    )
    (net (code "69") (name "unconnected-(IC3-L6-Pad12)") (class "Default")
      (node (ref "IC3") (pin "12") (pinfunction "L6_12") (pintype "output"))
    )
    (net (code "70") (name "unconnected-(IC3-L7-Pad13)") (class "Default")
      (node (ref "IC3") (pin "13") (pinfunction "L7_13") (pintype "output"))
    )
    (net (code "71") (name "unconnected-(IC3-L8-Pad15)") (class "Default")
      (node (ref "IC3") (pin "15") (pinfunction "L8_15") (pintype "output"))
    )
    (net (code "72") (name "unconnected-(IC3-L9-Pad16)") (class "Default")
      (node (ref "IC3") (pin "16") (pinfunction "L9_16") (pintype "output"))
    )
    (net (code "73") (name "unconnected-(IC3-L10-Pad17)") (class "Default")
      (node (ref "IC3") (pin "17") (pinfunction "L10_17") (pintype "output"))
    )
    (net (code "74") (name "unconnected-(IC3-L11-Pad18)") (class "Default")
      (node (ref "IC3") (pin "18") (pinfunction "L11_18") (pintype "output"))
    )
    (net (code "75") (name "unconnected-(IC3-L12-Pad19)") (class "Default")
      (node (ref "IC3") (pin "19") (pinfunction "L12_19") (pintype "output"))
    )
    (net (code "76") (name "unconnected-(IC3-L13-Pad20)") (class "Default")
      (node (ref "IC3") (pin "20") (pinfunction "L13_20") (pintype "output"))
    )
    (net (code "77") (name "unconnected-(IC3-L14-Pad21)") (class "Default")
      (node (ref "IC3") (pin "21") (pinfunction "L14_21") (pintype "output"))
    )
    (net (code "78") (name "unconnected-(IC3-L15-Pad22)") (class "Default")
      (node (ref "IC3") (pin "22") (pinfunction "L15_22") (pintype "output"))
    )
    (net (code "79") (name "unconnected-(SERIAL-Pad5)") (class "Default")
      (node (ref "SERIAL") (pin "5") (pinfunction "5_5") (pintype "passive"))
    )
    (net (code "80") (name "unconnected-(SERIAL-Pad6)") (class "Default")
      (node (ref "SERIAL") (pin "6") (pinfunction "6_6") (pintype "passive"))
    )
    (net (code "81") (name "unconnected-(SERIAL-Pad7)") (class "Default")
      (node (ref "SERIAL") (pin "7") (pinfunction "7_7") (pintype "passive"))
    )
    (net (code "82") (name "unconnected-(SERIAL-Pad8)") (class "Default")
      (node (ref "SERIAL") (pin "8") (pinfunction "8_8") (pintype "passive"))
    )
  )
)
